# RP5_Left_Flex.net
KiCad netlist of a schematic drawn in Altium Designer
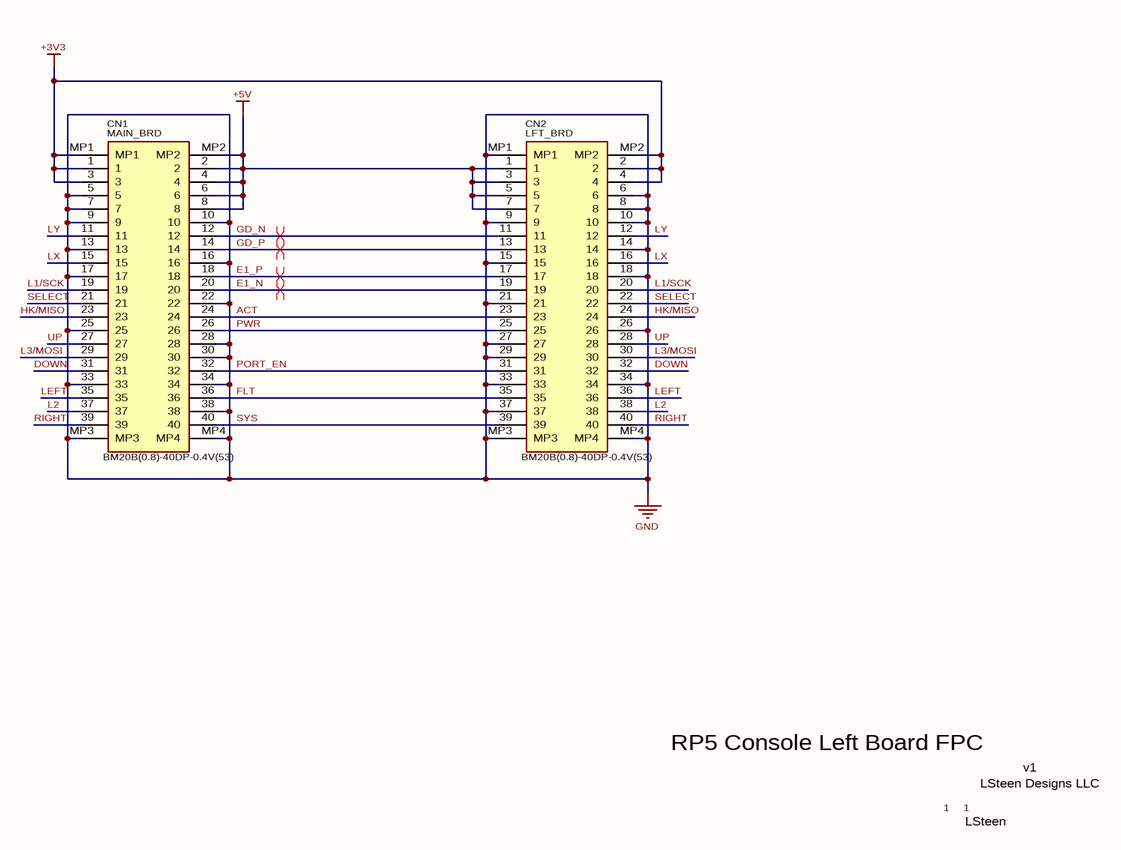
[diagram p0: RP5_Left_Flex.SchDoc]

(export (version "E")
  (design (tool "Eeschema 10.0.6"))
  (components
    (comp (ref "CN1")
      (value "MAIN_BRD")
      (footprint "BM20B0840DP04V53")
      (description "Connector")
      (fields (field (name "MANUFACTURER_PART_NUMBER") "BM20B(0.8)-40DP-0.4V(51)"))
      (libsource (lib "SamacSys") (part "BM20B(0.8)-40DP-0.4V(53)"))
    )
    (comp (ref "CN2")
      (value "LFT_BRD")
      (footprint "BM20B0840DP04V53")
      (description "Connector")
      (fields (field (name "MANUFACTURER_PART_NUMBER") "BM20B(0.8)-40DP-0.4V(51)"))
      (libsource (lib "SamacSys") (part "BM20B(0.8)-40DP-0.4V(53)"))
    )
  )
  (nets
    (net (code "1") (name "+3V3") (class "Default")
      (node (ref "CN1") (pin "1") (pinfunction "1_1") (pintype "passive"))
      (node (ref "CN1") (pin "3") (pinfunction "3_3") (pintype "passive"))
      (node (ref "CN1") (pin "MP1") (pinfunction "MP1_MP1") (pintype "passive"))
      (node (ref "CN2") (pin "2") (pinfunction "2_2") (pintype "passive"))
      (node (ref "CN2") (pin "4") (pinfunction "4_4") (pintype "passive"))
      (node (ref "CN2") (pin "MP2") (pinfunction "MP2_MP2") (pintype "passive"))
    )
    (net (code "2") (name "+5V") (class "Default")
      (node (ref "CN1") (pin "2") (pinfunction "2_2") (pintype "passive"))
      (node (ref "CN1") (pin "4") (pinfunction "4_4") (pintype "passive"))
      (node (ref "CN1") (pin "6") (pinfunction "6_6") (pintype "passive"))
      (node (ref "CN1") (pin "8") (pinfunction "8_8") (pintype "passive"))
      (node (ref "CN1") (pin "MP2") (pinfunction "MP2_MP2") (pintype "passive"))
      (node (ref "CN2") (pin "1") (pinfunction "1_1") (pintype "passive"))
      (node (ref "CN2") (pin "3") (pinfunction "3_3") (pintype "passive"))
      (node (ref "CN2") (pin "5") (pinfunction "5_5") (pintype "passive"))
      (node (ref "CN2") (pin "7") (pinfunction "7_7") (pintype "passive"))
    )
    (net (code "3") (name "/ACT") (class "Default")
      (node (ref "CN1") (pin "24") (pinfunction "24_24") (pintype "passive"))
      (node (ref "CN2") (pin "23") (pinfunction "23_23") (pintype "passive"))
    )
    (net (code "4") (name "/DOWN") (class "Default")
      (node (ref "CN1") (pin "31") (pinfunction "31_31") (pintype "passive"))
      (node (ref "CN2") (pin "32") (pinfunction "32_32") (pintype "passive"))
    )
    (net (code "5") (name "/E1_N") (class "Default")
      (node (ref "CN1") (pin "20") (pinfunction "20_20") (pintype "passive"))
      (node (ref "CN2") (pin "19") (pinfunction "19_19") (pintype "passive"))
    )
    (net (code "6") (name "/E1_P") (class "Default")
      (node (ref "CN1") (pin "18") (pinfunction "18_18") (pintype "passive"))
      (node (ref "CN2") (pin "17") (pinfunction "17_17") (pintype "passive"))
    )
    (net (code "7") (name "/FLT") (class "Default")
      (node (ref "CN1") (pin "36") (pinfunction "36_36") (pintype "passive"))
      (node (ref "CN2") (pin "35") (pinfunction "35_35") (pintype "passive"))
    )
    (net (code "8") (name "/GD_N") (class "Default")
      (node (ref "CN1") (pin "12") (pinfunction "12_12") (pintype "passive"))
      (node (ref "CN2") (pin "11") (pinfunction "11_11") (pintype "passive"))
    )
    (net (code "9") (name "/GD_P") (class "Default")
      (node (ref "CN1") (pin "14") (pinfunction "14_14") (pintype "passive"))
      (node (ref "CN2") (pin "13") (pinfunction "13_13") (pintype "passive"))
    )
    (net (code "10") (name "/HK{slash}MISO") (class "Default")
      (node (ref "CN1") (pin "23") (pinfunction "23_23") (pintype "passive"))
      (node (ref "CN2") (pin "24") (pinfunction "24_24") (pintype "passive"))
    )
    (net (code "11") (name "/L1{slash}SCK") (class "Default")
      (node (ref "CN1") (pin "19") (pinfunction "19_19") (pintype "passive"))
      (node (ref "CN2") (pin "20") (pinfunction "20_20") (pintype "passive"))
    )
    (net (code "12") (name "/L2") (class "Default")
      (node (ref "CN1") (pin "37") (pinfunction "37_37") (pintype "passive"))
      (node (ref "CN2") (pin "38") (pinfunction "38_38") (pintype "passive"))
    )
    (net (code "13") (name "/L3{slash}MOSI") (class "Default")
      (node (ref "CN1") (pin "29") (pinfunction "29_29") (pintype "passive"))
      (node (ref "CN2") (pin "30") (pinfunction "30_30") (pintype "passive"))
    )
    (net (code "14") (name "/LEFT") (class "Default")
      (node (ref "CN1") (pin "35") (pinfunction "35_35") (pintype "passive"))
      (node (ref "CN2") (pin "36") (pinfunction "36_36") (pintype "passive"))
    )
    (net (code "15") (name "/LX") (class "Default")
      (node (ref "CN1") (pin "15") (pinfunction "15_15") (pintype "passive"))
      (node (ref "CN2") (pin "16") (pinfunction "16_16") (pintype "passive"))
    )
    (net (code "16") (name "/LY") (class "Default")
      (node (ref "CN1") (pin "11") (pinfunction "11_11") (pintype "passive"))
      (node (ref "CN2") (pin "12") (pinfunction "12_12") (pintype "passive"))
    )
    (net (code "17") (name "/PORT_EN") (class "Default")
      (node (ref "CN1") (pin "32") (pinfunction "32_32") (pintype "passive"))
      (node (ref "CN2") (pin "31") (pinfunction "31_31") (pintype "passive"))
    )
    (net (code "18") (name "/PWR") (class "Default")
      (node (ref "CN1") (pin "26") (pinfunction "26_26") (pintype "passive"))
      (node (ref "CN2") (pin "25") (pinfunction "25_25") (pintype "passive"))
    )
    (net (code "19") (name "/RIGHT") (class "Default")
      (node (ref "CN1") (pin "39") (pinfunction "39_39") (pintype "passive"))
      (node (ref "CN2") (pin "40") (pinfunction "40_40") (pintype "passive"))
    )
    (net (code "20") (name "/SELECT") (class "Default")
      (node (ref "CN1") (pin "21") (pinfunction "21_21") (pintype "passive"))
      (node (ref "CN2") (pin "22") (pinfunction "22_22") (pintype "passive"))
    )
    (net (code "21") (name "/SYS") (class "Default")
      (node (ref "CN1") (pin "40") (pinfunction "40_40") (pintype "passive"))
      (node (ref "CN2") (pin "39") (pinfunction "39_39") (pintype "passive"))
    )
    (net (code "22") (name "/UP") (class "Default")
      (node (ref "CN1") (pin "27") (pinfunction "27_27") (pintype "passive"))
      (node (ref "CN2") (pin "28") (pinfunction "28_28") (pintype "passive"))
    )
    (net (code "23") (name "GND") (class "Default")
      (node (ref "CN1") (pin "10") (pinfunction "10_10") (pintype "passive"))
      (node (ref "CN1") (pin "13") (pinfunction "13_13") (pintype "passive"))
      (node (ref "CN1") (pin "16") (pinfunction "16_16") (pintype "passive"))
      (node (ref "CN1") (pin "17") (pinfunction "17_17") (pintype "passive"))
      (node (ref "CN1") (pin "22") (pinfunction "22_22") (pintype "passive"))
      (node (ref "CN1") (pin "25") (pinfunction "25_25") (pintype "passive"))
      (node (ref "CN1") (pin "28") (pinfunction "28_28") (pintype "passive"))
      (node (ref "CN1") (pin "30") (pinfunction "30_30") (pintype "passive"))
      (node (ref "CN1") (pin "33") (pinfunction "33_33") (pintype "passive"))
      (node (ref "CN1") (pin "34") (pinfunction "34_34") (pintype "passive"))
      (node (ref "CN1") (pin "38") (pinfunction "38_38") (pintype "passive"))
      (node (ref "CN1") (pin "5") (pinfunction "5_5") (pintype "passive"))
      (node (ref "CN1") (pin "7") (pinfunction "7_7") (pintype "passive"))
      (node (ref "CN1") (pin "9") (pinfunction "9_9") (pintype "passive"))
      (node (ref "CN1") (pin "MP3") (pinfunction "MP3_MP3") (pintype "passive"))
      (node (ref "CN1") (pin "MP4") (pinfunction "MP4_MP4") (pintype "passive"))
      (node (ref "CN2") (pin "10") (pinfunction "10_10") (pintype "passive"))
      (node (ref "CN2") (pin "14") (pinfunction "14_14") (pintype "passive"))
      (node (ref "CN2") (pin "15") (pinfunction "15_15") (pintype "passive"))
      (node (ref "CN2") (pin "18") (pinfunction "18_18") (pintype "passive"))
      (node (ref "CN2") (pin "21") (pinfunction "21_21") (pintype "passive"))
      (node (ref "CN2") (pin "26") (pinfunction "26_26") (pintype "passive"))
      (node (ref "CN2") (pin "27") (pinfunction "27_27") (pintype "passive"))
      (node (ref "CN2") (pin "29") (pinfunction "29_29") (pintype "passive"))
      (node (ref "CN2") (pin "33") (pinfunction "33_33") (pintype "passive"))
      (node (ref "CN2") (pin "34") (pinfunction "34_34") (pintype "passive"))
      (node (ref "CN2") (pin "37") (pinfunction "37_37") (pintype "passive"))
      (node (ref "CN2") (pin "6") (pinfunction "6_6") (pintype "passive"))
      (node (ref "CN2") (pin "8") (pinfunction "8_8") (pintype "passive"))
      (node (ref "CN2") (pin "9") (pinfunction "9_9") (pintype "passive"))
      (node (ref "CN2") (pin "MP1") (pinfunction "MP1_MP1") (pintype "passive"))
      (node (ref "CN2") (pin "MP3") (pinfunction "MP3_MP3") (pintype "passive"))
      (node (ref "CN2") (pin "MP4") (pinfunction "MP4_MP4") (pintype "passive"))
    )
  )
)
